# untitled.net
KiCad netlist of a schematic drawn in EAGLE
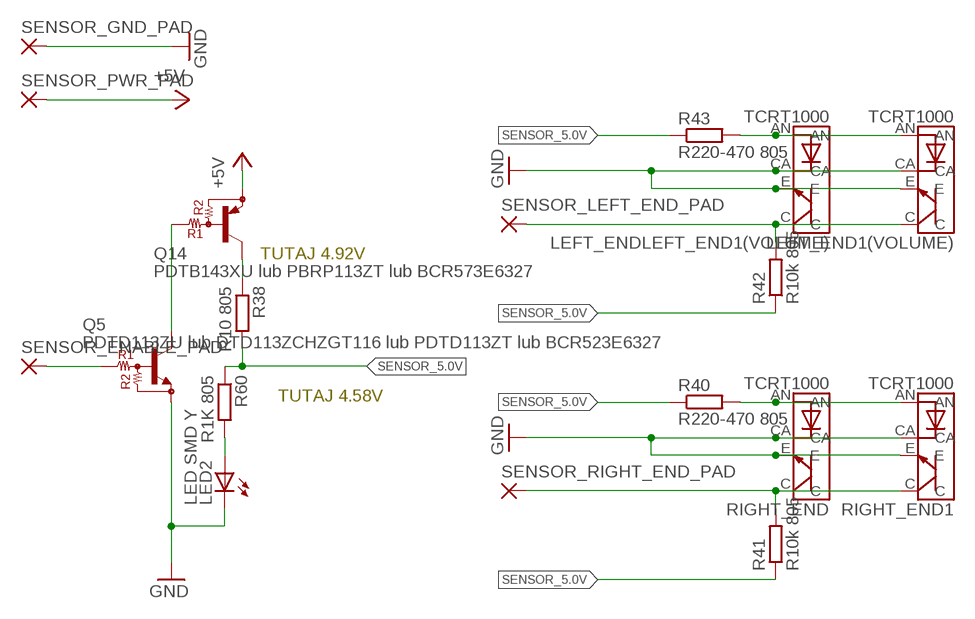
[diagram p0: schematic, sheet 1]

(export (version "E")
  (design (tool "Eeschema 10.0.6"))
  (components
    (comp (ref "LED2")
      (value "LED SMD Y")
      (footprint "eagle-import:CHIP-LED0805")
      (libsource (lib "eagle-import") (part "LEDCHIP-LED0805"))
    )
    (comp (ref "LEFT_END1(VOLUME)")
      (value "TCRT1000")
      (footprint "eagle-import:TCRT1000")
      (libsource (lib "eagle-import") (part "TCRT1000"))
    )
    (comp (ref "LEFT_ENDLEFT_END1(VOLUME)")
      (value "TCRT1000")
      (footprint "eagle-import:TCRT1000")
      (libsource (lib "eagle-import") (part "TCRT1000"))
    )
    (comp (ref "Q5")
      (value "PDTD113ZU lub DTD113ZCHZGT116 lub PDTD113ZT lub BCR523E6327")
      (footprint "eagle-import:SOT-23")
      (libsource (lib "eagle-import") (part "PDTD113ZU"))
    )
    (comp (ref "Q14")
      (value "PDTB143XU lub PBRP113ZT lub BCR573E6327")
      (footprint "eagle-import:SOT-23")
      (libsource (lib "eagle-import") (part "PDTB143XU"))
    )
    (comp (ref "R38")
      (value "R10 805")
      (footprint "eagle-import:R0805")
      (libsource (lib "eagle-import") (part "R-EU_R0805"))
    )
    (comp (ref "R40")
      (value "R220-470 805")
      (footprint "eagle-import:M0805")
      (libsource (lib "eagle-import") (part "R-EU_M0805"))
    )
    (comp (ref "R41")
      (value "R10k 805")
      (footprint "eagle-import:M0805")
      (libsource (lib "eagle-import") (part "R-EU_M0805"))
    )
    (comp (ref "R42")
      (value "R10k 805")
      (footprint "eagle-import:M0805")
      (libsource (lib "eagle-import") (part "R-EU_M0805"))
    )
    (comp (ref "R43")
      (value "R220-470 805")
      (footprint "eagle-import:M0805")
      (libsource (lib "eagle-import") (part "R-EU_M0805"))
    )
    (comp (ref "R60")
      (value "R1K 805")
      (footprint "eagle-import:R0805")
      (libsource (lib "eagle-import") (part "R-EU_R0805"))
    )
    (comp (ref "RIGHT_END")
      (value "TCRT1000")
      (footprint "eagle-import:TCRT1000")
      (libsource (lib "eagle-import") (part "TCRT1000"))
    )
    (comp (ref "RIGHT_END1")
      (value "TCRT1000")
      (footprint "eagle-import:TCRT1000")
      (libsource (lib "eagle-import") (part "TCRT1000"))
    )
    (comp (ref "SENSOR_ENABLE_PAD")
      (value "SMD2")
      (footprint "eagle-import:SMD1,27-2,54")
      (libsource (lib "eagle-import") (part "SMD2"))
    )
    (comp (ref "SENSOR_GND_PAD")
      (value "SMD2")
      (footprint "eagle-import:SMD1,27-2,54")
      (libsource (lib "eagle-import") (part "SMD2"))
    )
    (comp (ref "SENSOR_LEFT_END_PAD")
      (value "SMD2")
      (footprint "eagle-import:SMD1,27-2,54")
      (libsource (lib "eagle-import") (part "SMD2"))
    )
    (comp (ref "SENSOR_PWR_PAD")
      (value "SMD2")
      (footprint "eagle-import:SMD1,27-2,54")
      (libsource (lib "eagle-import") (part "SMD2"))
    )
    (comp (ref "SENSOR_RIGHT_END_PAD")
      (value "SMD2")
      (footprint "eagle-import:SMD1,27-2,54")
      (libsource (lib "eagle-import") (part "SMD2"))
    )
  )
  (nets
    (net (code "1") (name "+5V") (class "Default")
      (node (ref "Q14") (pin "2") (pinfunction "E_2") (pintype "passive"))
      (node (ref "SENSOR_PWR_PAD") (pin "1") (pinfunction "P_1") (pintype "passive"))
    )
    (net (code "2") (name "GND") (class "Default")
      (node (ref "LED2") (pin "C") (pinfunction "C_C") (pintype "passive"))
      (node (ref "LEFT_END1(VOLUME)") (pin "CA") (pinfunction "CA_CA") (pintype "passive"))
      (node (ref "LEFT_END1(VOLUME)") (pin "E") (pinfunction "E_E") (pintype "passive"))
      (node (ref "LEFT_ENDLEFT_END1(VOLUME)") (pin "CA") (pinfunction "CA_CA") (pintype "passive"))
      (node (ref "LEFT_ENDLEFT_END1(VOLUME)") (pin "E") (pinfunction "E_E") (pintype "passive"))
      (node (ref "Q5") (pin "2") (pinfunction "E_2") (pintype "passive"))
      (node (ref "RIGHT_END") (pin "CA") (pinfunction "CA_CA") (pintype "passive"))
      (node (ref "RIGHT_END") (pin "E") (pinfunction "E_E") (pintype "passive"))
      (node (ref "RIGHT_END1") (pin "CA") (pinfunction "CA_CA") (pintype "passive"))
      (node (ref "RIGHT_END1") (pin "E") (pinfunction "E_E") (pintype "passive"))
      (node (ref "SENSOR_GND_PAD") (pin "1") (pinfunction "P_1") (pintype "passive"))
    )
    (net (code "3") (name "Net-(LED2-PadA)") (class "Default")
      (node (ref "LED2") (pin "A") (pinfunction "A_A") (pintype "passive"))
      (node (ref "R60") (pin "2") (pinfunction "2_2") (pintype "passive"))
    )
    (net (code "4") (name "Net-(LEFT_END1(VOLUME)-PadAN)") (class "Default")
      (node (ref "LEFT_END1(VOLUME)") (pin "AN") (pinfunction "AN_AN") (pintype "passive"))
      (node (ref "LEFT_ENDLEFT_END1(VOLUME)") (pin "AN") (pinfunction "AN_AN") (pintype "passive"))
      (node (ref "R43") (pin "2") (pinfunction "2_2") (pintype "passive"))
    )
    (net (code "5") (name "Net-(Q5-B)") (class "Default")
      (node (ref "Q5") (pin "1") (pinfunction "B_1") (pintype "passive"))
      (node (ref "SENSOR_ENABLE_PAD") (pin "1") (pinfunction "P_1") (pintype "passive"))
    )
    (net (code "6") (name "Net-(Q14-B)") (class "Default")
      (node (ref "Q14") (pin "1") (pinfunction "B_1") (pintype "passive"))
      (node (ref "Q5") (pin "3") (pinfunction "C_3") (pintype "passive"))
    )
    (net (code "7") (name "Net-(Q14-C)") (class "Default")
      (node (ref "Q14") (pin "3") (pinfunction "C_3") (pintype "passive"))
      (node (ref "R38") (pin "1") (pinfunction "1_1") (pintype "passive"))
    )
    (net (code "8") (name "Net-(R40-Pad2)") (class "Default")
      (node (ref "R40") (pin "2") (pinfunction "2_2") (pintype "passive"))
      (node (ref "RIGHT_END") (pin "AN") (pinfunction "AN_AN") (pintype "passive"))
      (node (ref "RIGHT_END1") (pin "AN") (pinfunction "AN_AN") (pintype "passive"))
    )
    (net (code "9") (name "Net-(SENSOR_LEFT_END_PAD-P)") (class "Default")
      (node (ref "LEFT_END1(VOLUME)") (pin "C") (pinfunction "C_C") (pintype "passive"))
      (node (ref "LEFT_ENDLEFT_END1(VOLUME)") (pin "C") (pinfunction "C_C") (pintype "passive"))
      (node (ref "R42") (pin "2") (pinfunction "2_2") (pintype "passive"))
      (node (ref "SENSOR_LEFT_END_PAD") (pin "1") (pinfunction "P_1") (pintype "passive"))
    )
    (net (code "10") (name "Net-(SENSOR_RIGHT_END_PAD-P)") (class "Default")
      (node (ref "R41") (pin "2") (pinfunction "2_2") (pintype "passive"))
      (node (ref "RIGHT_END") (pin "C") (pinfunction "C_C") (pintype "passive"))
      (node (ref "RIGHT_END1") (pin "C") (pinfunction "C_C") (pintype "passive"))
      (node (ref "SENSOR_RIGHT_END_PAD") (pin "1") (pinfunction "P_1") (pintype "passive"))
    )
    (net (code "11") (name "SENSOR_5.0V") (class "Default")
      (node (ref "R38") (pin "2") (pinfunction "2_2") (pintype "passive"))
      (node (ref "R40") (pin "1") (pinfunction "1_1") (pintype "passive"))
      (node (ref "R41") (pin "1") (pinfunction "1_1") (pintype "passive"))
      (node (ref "R42") (pin "1") (pinfunction "1_1") (pintype "passive"))
      (node (ref "R43") (pin "1") (pinfunction "1_1") (pintype "passive"))
      (node (ref "R60") (pin "1") (pinfunction "1_1") (pintype "passive"))
    )
  )
)
